# QFN-16_with_EP_to_DIP-17.net
KiCad netlist of a schematic drawn in EAGLE
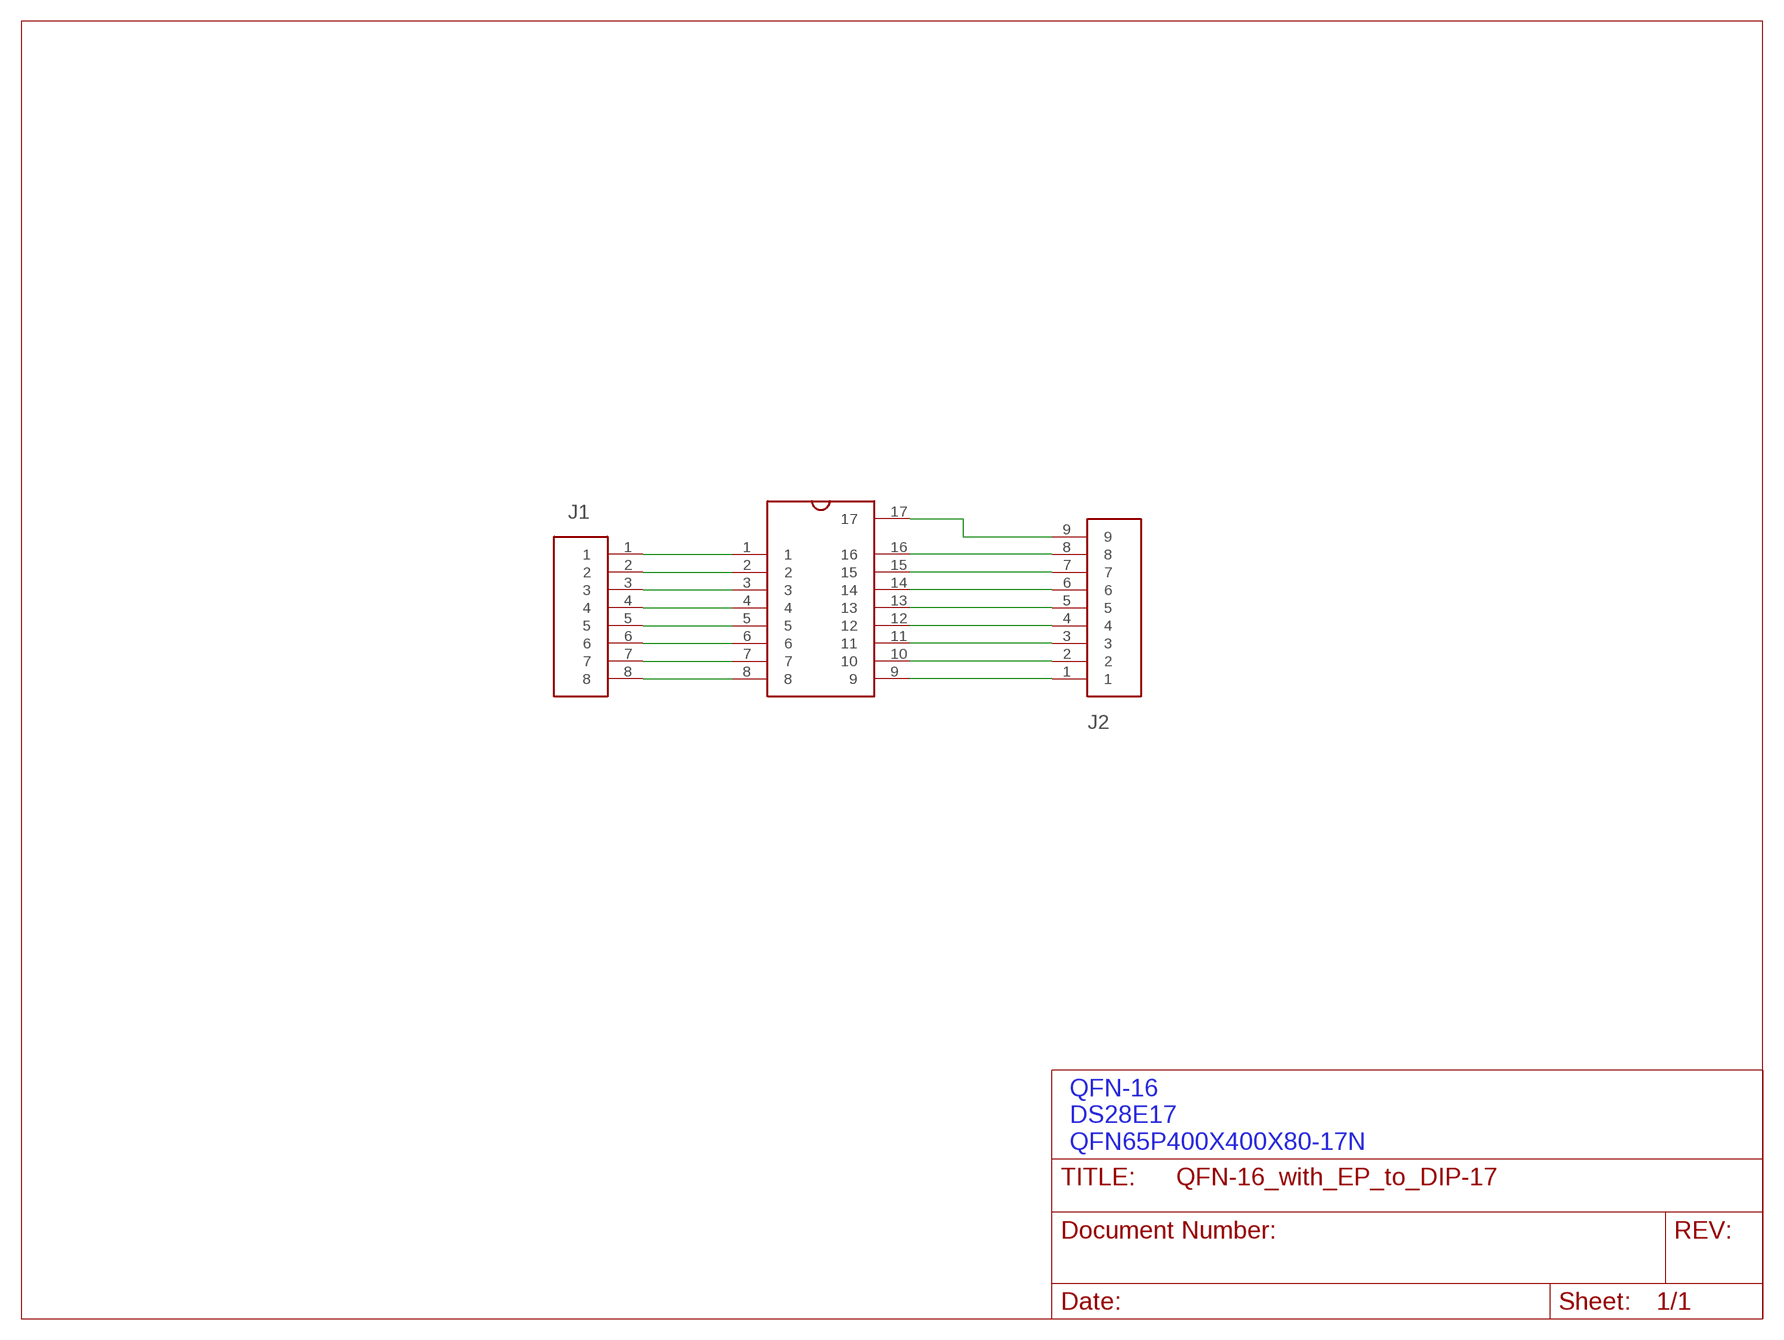
[diagram p0: schematic, sheet 1]

(export (version "E")
  (design (tool "Eeschema 10.0.6"))
  (components
    (comp (ref "J1")
      (value "CONNECTOR_8")
      (footprint "eagle-import:68000-108HLF")
      (libsource (lib "eagle-import") (part "CONNECTOR_8"))
    )
    (comp (ref "J2")
      (value "CONNECTOR_9")
      (footprint "eagle-import:68000-109HLF-NO-SQUARE")
      (libsource (lib "eagle-import") (part "CONNECTOR_9"))
    )
    (comp (ref "U1")
      (value "QFN-16_WITH_EP-QFN-16_EP")
      (footprint "eagle-import:QFN65P400X400X80-17N")
      (libsource (lib "eagle-import") (part "QFN-16_WITH_EP-QFN-16_EP"))
    )
  )
  (nets
    (net (code "1") (name "Net-(J1-Pad1)") (class "Default")
      (node (ref "J1") (pin "1") (pinfunction "1_1") (pintype "bidirectional"))
      (node (ref "U1") (pin "1") (pinfunction "1_1") (pintype "bidirectional"))
    )
    (net (code "2") (name "Net-(J1-Pad2)") (class "Default")
      (node (ref "J1") (pin "2") (pinfunction "2_2") (pintype "bidirectional"))
      (node (ref "U1") (pin "2") (pinfunction "2_2") (pintype "bidirectional"))
    )
    (net (code "3") (name "Net-(J1-Pad3)") (class "Default")
      (node (ref "J1") (pin "3") (pinfunction "3_3") (pintype "bidirectional"))
      (node (ref "U1") (pin "3") (pinfunction "3_3") (pintype "bidirectional"))
    )
    (net (code "4") (name "Net-(J1-Pad4)") (class "Default")
      (node (ref "J1") (pin "4") (pinfunction "4_4") (pintype "bidirectional"))
      (node (ref "U1") (pin "4") (pinfunction "4_4") (pintype "bidirectional"))
    )
    (net (code "5") (name "Net-(J1-Pad5)") (class "Default")
      (node (ref "J1") (pin "5") (pinfunction "5_5") (pintype "bidirectional"))
      (node (ref "U1") (pin "5") (pinfunction "5_5") (pintype "bidirectional"))
    )
    (net (code "6") (name "Net-(J1-Pad6)") (class "Default")
      (node (ref "J1") (pin "6") (pinfunction "6_6") (pintype "bidirectional"))
      (node (ref "U1") (pin "6") (pinfunction "6_6") (pintype "bidirectional"))
    )
    (net (code "7") (name "Net-(J1-Pad7)") (class "Default")
      (node (ref "J1") (pin "7") (pinfunction "7_7") (pintype "bidirectional"))
      (node (ref "U1") (pin "7") (pinfunction "7_7") (pintype "bidirectional"))
    )
    (net (code "8") (name "Net-(J1-Pad8)") (class "Default")
      (node (ref "J1") (pin "8") (pinfunction "8_8") (pintype "bidirectional"))
      (node (ref "U1") (pin "8") (pinfunction "8_8") (pintype "bidirectional"))
    )
    (net (code "9") (name "Net-(J2-Pad1)") (class "Default")
      (node (ref "J2") (pin "1") (pinfunction "1_1") (pintype "bidirectional"))
      (node (ref "U1") (pin "9") (pinfunction "9_9") (pintype "bidirectional"))
    )
    (net (code "10") (name "Net-(J2-Pad2)") (class "Default")
      (node (ref "J2") (pin "2") (pinfunction "2_2") (pintype "bidirectional"))
      (node (ref "U1") (pin "10") (pinfunction "10_10") (pintype "bidirectional"))
    )
    (net (code "11") (name "Net-(J2-Pad3)") (class "Default")
      (node (ref "J2") (pin "3") (pinfunction "3_3") (pintype "bidirectional"))
      (node (ref "U1") (pin "11") (pinfunction "11_11") (pintype "bidirectional"))
    )
    (net (code "12") (name "Net-(J2-Pad4)") (class "Default")
      (node (ref "J2") (pin "4") (pinfunction "4_4") (pintype "bidirectional"))
      (node (ref "U1") (pin "12") (pinfunction "12_12") (pintype "bidirectional"))
    )
    (net (code "13") (name "Net-(J2-Pad5)") (class "Default")
      (node (ref "J2") (pin "5") (pinfunction "5_5") (pintype "bidirectional"))
      (node (ref "U1") (pin "13") (pinfunction "13_13") (pintype "bidirectional"))
    )
    (net (code "14") (name "Net-(J2-Pad6)") (class "Default")
      (node (ref "J2") (pin "6") (pinfunction "6_6") (pintype "bidirectional"))
      (node (ref "U1") (pin "14") (pinfunction "14_14") (pintype "bidirectional"))
    )
    (net (code "15") (name "Net-(J2-Pad7)") (class "Default")
      (node (ref "J2") (pin "7") (pinfunction "7_7") (pintype "bidirectional"))
      (node (ref "U1") (pin "15") (pinfunction "15_15") (pintype "bidirectional"))
    )
    (net (code "16") (name "Net-(J2-Pad8)") (class "Default")
      (node (ref "J2") (pin "8") (pinfunction "8_8") (pintype "bidirectional"))
      (node (ref "U1") (pin "16") (pinfunction "16_16") (pintype "bidirectional"))
    )
    (net (code "17") (name "Net-(J2-Pad9)") (class "Default")
      (node (ref "J2") (pin "9") (pinfunction "9_9") (pintype "bidirectional"))
      (node (ref "U1") (pin "17") (pinfunction "17_17") (pintype "bidirectional"))
    )
  )
)
